# 09_CAN_Bus.net
KiCad netlist of a schematic drawn in Altium Designer
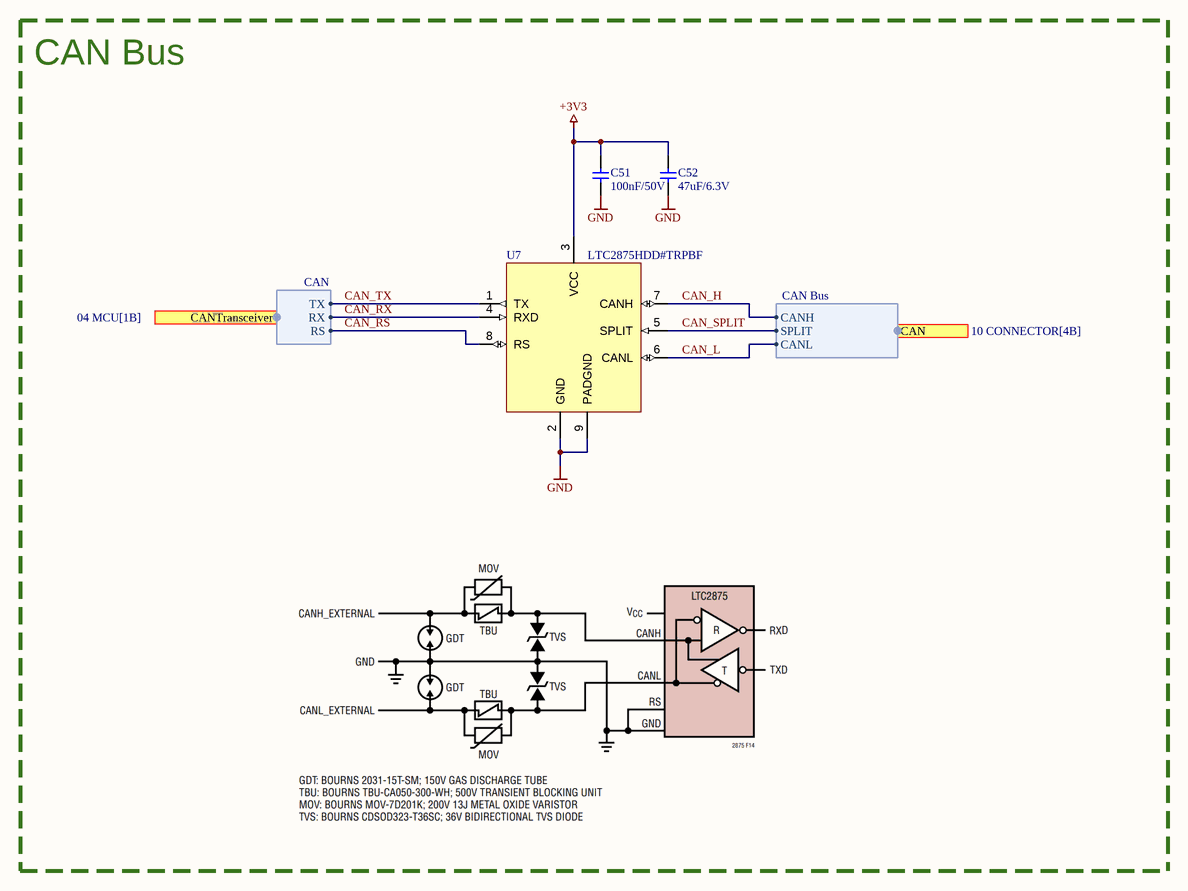
[diagram p0: 09 CAN Bus.SchDoc]

(export (version "E")
  (design (tool "Eeschema 10.0.6"))
  (components
    (comp (ref "C51")
      (value "100nF/50V")
      (footprint "CAPC1005X06M-0402")
      (description "0.1 µF ±10% 50V Ceramic Capacitor X7R 0402 (1005 Metric)")
      (fields (field (name "MPN") "GRM155R71H104KE14D"))
      (libsource (lib "Symbol") (part "GRM155R71H104KE14D"))
    )
    (comp (ref "C52")
      (value "47uF/6.3V")
      (footprint "CAPC1608X10M-0603")
      (description "47 µF ±20% 6.3V Ceramic Capacitor X5R 0603 (1608 Metric)")
      (fields (field (name "MPN") "GRM188R60J476ME15D"))
      (libsource (lib "Symbol") (part "GRM188R60J476ME15D"))
    )
    (comp (ref "U7")
      (value "LTC2875HDD#TRPBF")
      (footprint "DFN-8")
      (description "1/1 Transceiver CANbus 8-DFN (3x3)")
      (libsource (lib "Symbol") (part "LTC2875HDD#TRPBF"))
    )
  )
  (nets
    (net (code "3") (name "+3V3") (class "Default")
      (node (ref "C51") (pin "2") (pinfunction "2_2") (pintype "passive"))
      (node (ref "C52") (pin "2") (pinfunction "2_2") (pintype "passive"))
      (node (ref "U7") (pin "3") (pinfunction "VCC_3") (pintype "power_in"))
    )
    (net (code "4") (name "/CAN_H") (class "Default")
      (node (ref "U7") (pin "7") (pinfunction "CANH_7") (pintype "bidirectional"))
    )
    (net (code "5") (name "/CAN_L") (class "Default")
      (node (ref "U7") (pin "6") (pinfunction "CANL_6") (pintype "bidirectional"))
    )
    (net (code "6") (name "/CAN_RS") (class "Default")
      (node (ref "U7") (pin "8") (pinfunction "RS_8") (pintype "bidirectional"))
    )
    (net (code "7") (name "/CAN_RX") (class "Default")
      (node (ref "U7") (pin "4") (pinfunction "RXD_4") (pintype "input"))
    )
    (net (code "8") (name "/CAN_SPLIT") (class "Default")
      (node (ref "U7") (pin "5") (pinfunction "SPLIT_5") (pintype "input"))
    )
    (net (code "9") (name "/CAN_TX") (class "Default")
      (node (ref "U7") (pin "1") (pinfunction "TX_1") (pintype "output"))
    )
    (net (code "12") (name "GND") (class "Default")
      (node (ref "C51") (pin "1") (pinfunction "1_1") (pintype "passive"))
      (node (ref "C52") (pin "1") (pinfunction "1_1") (pintype "passive"))
      (node (ref "U7") (pin "2") (pinfunction "GND_2") (pintype "power_in"))
      (node (ref "U7") (pin "9") (pinfunction "PADGND_9") (pintype "power_in"))
    )
  )
)
